# SCH_Plantcare_Module-v3_2024-10-27.net
KiCad netlist of a schematic drawn in EasyEDA
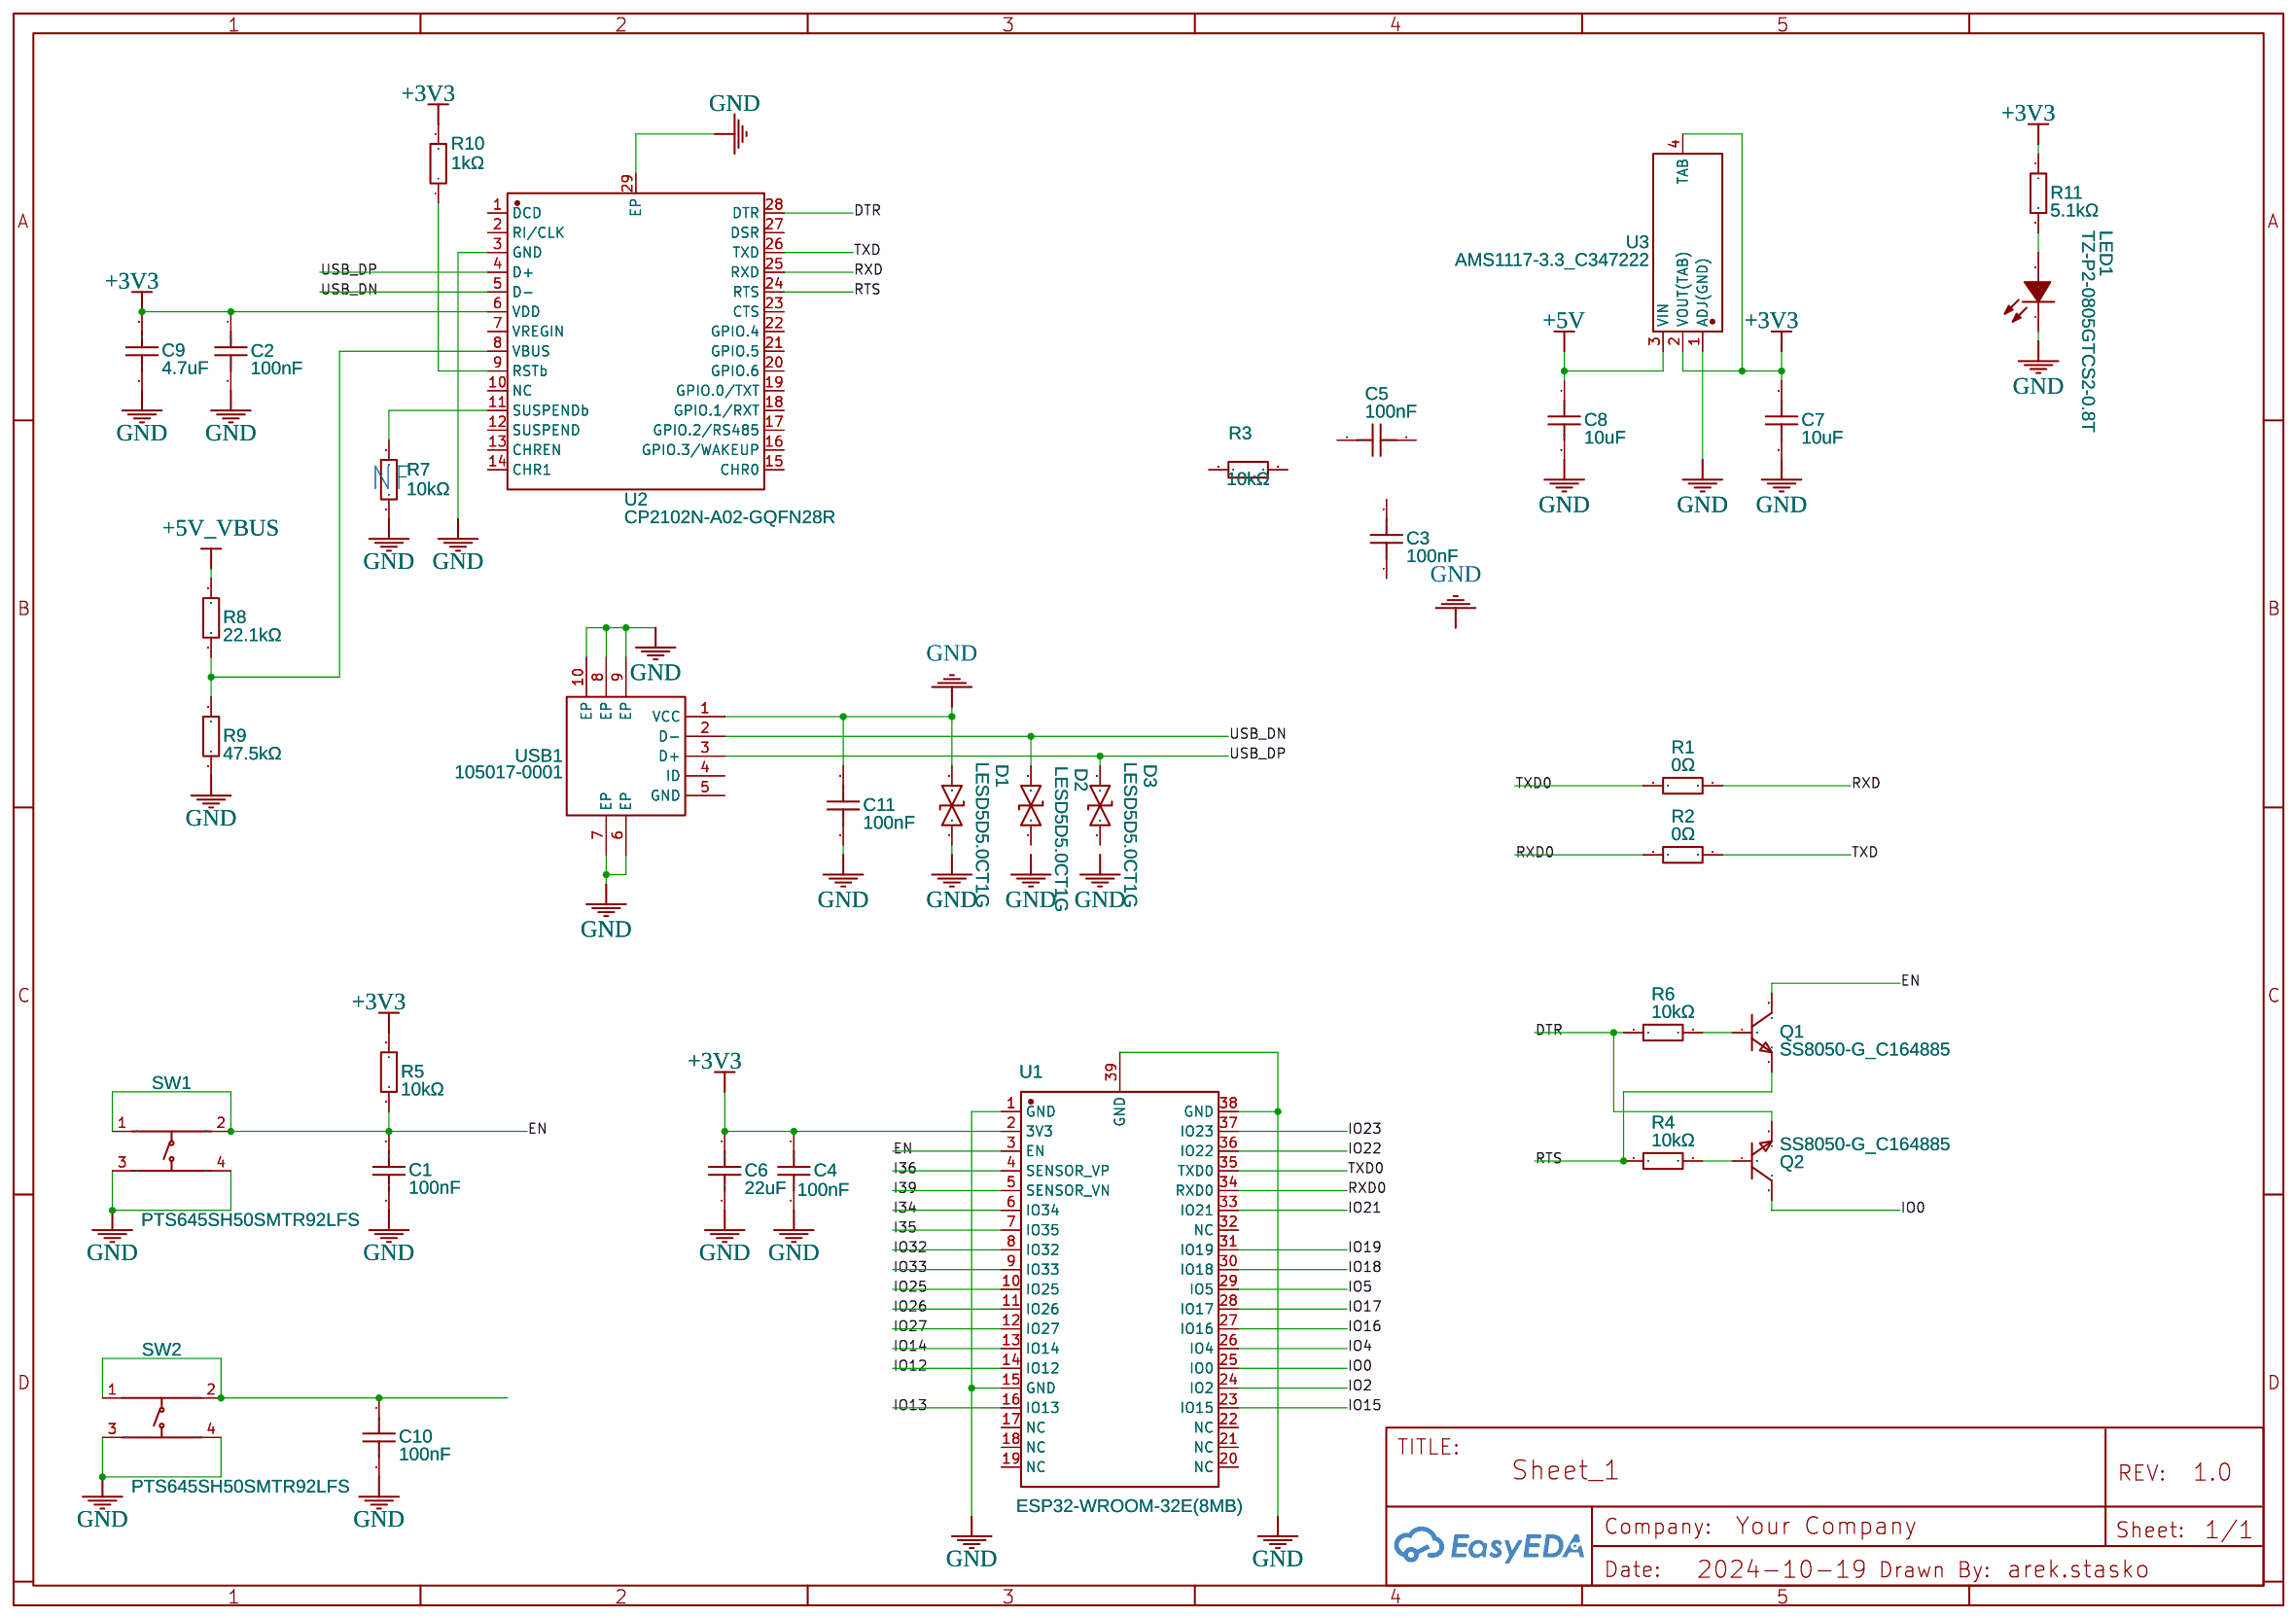
[diagram p0: schematic sheet]

(export (version "E")
  (design (tool "Eeschema 10.0.6"))
  (components
    (comp (ref "C1")
      (value "100nF")
      (fields
        (field (name "Manufacturer Part") "CL05B104KO5NNNC")
        (field (name "Manufacturer") "SAMSUNG(三星)")
      )
      (libsource (lib "") (part "CL05B104KO5NNNC"))
    )
    (comp (ref "C2")
      (value "100nF")
      (fields
        (field (name "Manufacturer Part") "CL05B104KO5NNNC")
        (field (name "Manufacturer") "SAMSUNG(三星)")
      )
      (libsource (lib "") (part "CL05B104KO5NNNC"))
    )
    (comp (ref "C3")
      (value "100nF")
      (fields
        (field (name "Manufacturer Part") "CL05B104KO5NNNC")
        (field (name "Manufacturer") "SAMSUNG(三星)")
      )
      (libsource (lib "") (part "CL05B104KO5NNNC"))
    )
    (comp (ref "C4")
      (value "100nF")
      (fields
        (field (name "Manufacturer Part") "CL05B104KO5NNNC")
        (field (name "Manufacturer") "SAMSUNG(三星)")
      )
      (libsource (lib "") (part "CL05B104KO5NNNC"))
    )
    (comp (ref "C5")
      (value "100nF")
      (fields
        (field (name "Manufacturer Part") "CL05B104KO5NNNC")
        (field (name "Manufacturer") "SAMSUNG(三星)")
      )
      (libsource (lib "") (part "CL05B104KO5NNNC_1"))
    )
    (comp (ref "C6")
      (value "22uF")
      (fields
        (field (name "Manufacturer Part") "CL21A226MAYNNNE")
        (field (name "Manufacturer") "SAMSUNG(三星)")
      )
      (libsource (lib "") (part "CL21A226MAYNNNE"))
    )
    (comp (ref "C7")
      (value "10uF")
      (fields
        (field (name "Manufacturer Part") "CL05A106MP5NUNC")
        (field (name "Manufacturer") "SAMSUNG(三星)")
      )
      (libsource (lib "") (part "CL05A106MP5NUNC_C315248"))
    )
    (comp (ref "C8")
      (value "10uF")
      (fields
        (field (name "Manufacturer Part") "CL05A106MP5NUNC")
        (field (name "Manufacturer") "SAMSUNG(三星)")
      )
      (libsource (lib "") (part "CL05A106MP5NUNC_C315248"))
    )
    (comp (ref "C9")
      (value "4.7uF")
      (fields
        (field (name "Manufacturer Part") "CL05A475KP5NRNC")
        (field (name "Manufacturer") "SAMSUNG(三星)")
      )
      (libsource (lib "") (part "CL05A475KP5NRNC"))
    )
    (comp (ref "C10")
      (value "100nF")
      (fields
        (field (name "Manufacturer Part") "CL05B104KO5NNNC")
        (field (name "Manufacturer") "SAMSUNG(三星)")
      )
      (libsource (lib "") (part "CL05B104KO5NNNC"))
    )
    (comp (ref "C11")
      (value "100nF")
      (fields
        (field (name "Manufacturer Part") "CL05B104KO5NNNC")
        (field (name "Manufacturer") "SAMSUNG(三星)")
      )
      (libsource (lib "") (part "CL05B104KO5NNNC"))
    )
    (comp (ref "D1")
      (value "LESD5D5.0CT1G")
      (fields (field (name "Manufacturer") "LRC(乐山无线电)"))
      (libsource (lib "") (part "LESD5D5.0CT1G_1"))
    )
    (comp (ref "D2")
      (value "LESD5D5.0CT1G")
      (fields (field (name "Manufacturer") "LRC(乐山无线电)"))
      (libsource (lib "") (part "LESD5D5.0CT1G"))
    )
    (comp (ref "D3")
      (value "LESD5D5.0CT1G")
      (fields (field (name "Manufacturer") "LRC(乐山无线电)"))
      (libsource (lib "") (part "LESD5D5.0CT1G"))
    )
    (comp (ref "LED1")
      (value "TZ-P2-0805GTCS2-0.8T")
      (fields (field (name "Manufacturer") "TUOZHAN(拓展光电)"))
      (libsource (lib "") (part "TZ-P2-0805GTCS2-0.8T"))
    )
    (comp (ref "Q1")
      (value "SS8050-G_C164885")
      (fields (field (name "Manufacturer Part") "SS8050-G") (field (name "Manufacturer") "CJ(江苏长电/长晶)"))
      (libsource (lib "") (part "SS8050-G_C164885_1"))
    )
    (comp (ref "Q2")
      (value "SS8050-G_C164885")
      (fields (field (name "Manufacturer Part") "SS8050-G") (field (name "Manufacturer") "CJ(江苏长电/长晶)"))
      (libsource (lib "") (part "SS8050-G_C164885"))
    )
    (comp (ref "R1")
      (value "0Ω")
      (fields
        (field (name "Manufacturer Part") "0402WGF0000TCE")
        (field (name "Manufacturer") "UNI-ROYAL(厚声)")
      )
      (libsource (lib "") (part "0402WGF0000TCE"))
    )
    (comp (ref "R2")
      (value "0Ω")
      (fields
        (field (name "Manufacturer Part") "0402WGF0000TCE")
        (field (name "Manufacturer") "UNI-ROYAL(厚声)")
      )
      (libsource (lib "") (part "0402WGF0000TCE"))
    )
    (comp (ref "R3")
      (value "10kΩ")
      (fields
        (field (name "Manufacturer Part") "0402WGF1002TCE")
        (field (name "Manufacturer") "UNI-ROYAL(厚声)")
      )
      (libsource (lib "") (part "0402WGF1002TCE_1"))
    )
    (comp (ref "R4")
      (value "10kΩ")
      (fields
        (field (name "Manufacturer Part") "0402WGF1002TCE")
        (field (name "Manufacturer") "UNI-ROYAL(厚声)")
      )
      (libsource (lib "") (part "0402WGF1002TCE_1"))
    )
    (comp (ref "R5")
      (value "10kΩ")
      (fields
        (field (name "Manufacturer Part") "0402WGF1002TCE")
        (field (name "Manufacturer") "UNI-ROYAL(厚声)")
      )
      (libsource (lib "") (part "0402WGF1002TCE"))
    )
    (comp (ref "R6")
      (value "10kΩ")
      (fields
        (field (name "Manufacturer Part") "0402WGF1002TCE")
        (field (name "Manufacturer") "UNI-ROYAL(厚声)")
      )
      (libsource (lib "") (part "0402WGF1002TCE_1"))
    )
    (comp (ref "R7")
      (value "10kΩ")
      (fields
        (field (name "Manufacturer Part") "0402WGF1002TCE")
        (field (name "Manufacturer") "UNI-ROYAL(厚声)")
      )
      (libsource (lib "") (part "0402WGF1002TCE"))
    )
    (comp (ref "R8")
      (value "22.1kΩ")
      (fields
        (field (name "Manufacturer Part") "0402WGF2212TCE")
        (field (name "Manufacturer") "UNI-ROYAL(厚声)")
      )
      (libsource (lib "") (part "0402WGF2212TCE"))
    )
    (comp (ref "R9")
      (value "47.5kΩ")
      (fields
        (field (name "Manufacturer Part") "0402WGF4752TCE")
        (field (name "Manufacturer") "UNI-ROYAL(厚声)")
      )
      (libsource (lib "") (part "0402WGF4752TCE"))
    )
    (comp (ref "R10")
      (value "1kΩ")
      (fields
        (field (name "Manufacturer Part") "0402WGF1001TCE")
        (field (name "Manufacturer") "UNI-ROYAL(厚声)")
      )
      (libsource (lib "") (part "0402WGF1001TCE"))
    )
    (comp (ref "R11")
      (value "5.1kΩ")
      (fields
        (field (name "Manufacturer Part") "0402WGF5101TCE")
        (field (name "Manufacturer") "UNI-ROYAL(厚声)")
      )
      (libsource (lib "") (part "0402WGF5101TCE"))
    )
    (comp (ref "SW1")
      (value "PTS645SH50SMTR92LFS")
      (fields (field (name "Manufacturer") "C&K"))
      (libsource (lib "") (part "PTS645SH50SMTR92LFS"))
    )
    (comp (ref "SW2")
      (value "PTS645SH50SMTR92LFS")
      (fields (field (name "Manufacturer") "C&K"))
      (libsource (lib "") (part "PTS645SH50SMTR92LFS"))
    )
    (comp (ref "U1")
      (value "ESP32-WROOM-32E(8MB)")
      (fields
        (field (name "Manufacturer Part") "ESP32-WROOM-32E-N8")
        (field (name "Manufacturer") "ESPRESSIF(乐鑫)")
      )
      (libsource (lib "") (part "ESP32-WROOM-32E(8MB)"))
    )
    (comp (ref "U2")
      (value "CP2102N-A02-GQFN28R")
      (fields (field (name "Manufacturer") "SKYWORKS/SILICON LABS(芯科)"))
      (libsource (lib "") (part "CP2102N-A02-GQFN28R"))
    )
    (comp (ref "U3")
      (value "AMS1117-3.3_C347222")
      (fields (field (name "Manufacturer Part") "AMS1117-3.3") (field (name "Manufacturer") "UMW(友台半导体)"))
      (libsource (lib "") (part "AMS1117-3.3_C347222"))
    )
    (comp (ref "USB1")
      (value "105017-0001")
      (fields (field (name "Manufacturer Part") "1050170001") (field (name "Manufacturer") "MOLEX"))
      (libsource (lib "") (part "105017-0001"))
    )
  )
  (nets
    (net (code "1") (name "+3V3") (class "Default")
      (node (ref "C2") (pin "1") (pinfunction "1_1") (pintype "unspecified"))
      (node (ref "C4") (pin "1") (pinfunction "1_1") (pintype "unspecified"))
      (node (ref "C6") (pin "1") (pinfunction "1_1") (pintype "unspecified"))
      (node (ref "C7") (pin "1") (pinfunction "1_1") (pintype "unspecified"))
      (node (ref "C9") (pin "2") (pinfunction "2_2") (pintype "unspecified"))
      (node (ref "R10") (pin "2") (pinfunction "2_2") (pintype "input"))
      (node (ref "R11") (pin "1") (pinfunction "1_1") (pintype "input"))
      (node (ref "R5") (pin "1") (pinfunction "1_1") (pintype "input"))
      (node (ref "U1") (pin "2") (pinfunction "3V3_2") (pintype "unspecified"))
      (node (ref "U2") (pin "6") (pinfunction "VDD_6") (pintype "unspecified"))
      (node (ref "U3") (pin "2") (pinfunction "VOUT(TAB)_2") (pintype "unspecified"))
      (node (ref "U3") (pin "4") (pinfunction "TAB_4") (pintype "unspecified"))
    )
    (net (code "2") (name "+5V") (class "Default")
      (node (ref "C8") (pin "1") (pinfunction "1_1") (pintype "unspecified"))
      (node (ref "U3") (pin "3") (pinfunction "VIN_3") (pintype "unspecified"))
    )
    (net (code "3") (name "+5V_VBUS") (class "Default")
      (node (ref "R8") (pin "1") (pinfunction "1_1") (pintype "input"))
    )
    (net (code "4") (name "/DTR") (class "Default")
      (node (ref "Q2") (pin "2") (pinfunction "E_2") (pintype "unspecified"))
      (node (ref "R6") (pin "1") (pinfunction "1_1") (pintype "input"))
      (node (ref "U2") (pin "28") (pinfunction "DTR_28") (pintype "unspecified"))
    )
    (net (code "5") (name "/EN") (class "Default")
      (node (ref "C1") (pin "1") (pinfunction "1_1") (pintype "unspecified"))
      (node (ref "Q1") (pin "3") (pinfunction "C_3") (pintype "unspecified"))
      (node (ref "R5") (pin "2") (pinfunction "2_2") (pintype "input"))
      (node (ref "SW1") (pin "1") (pinfunction "1_1") (pintype "unspecified"))
      (node (ref "SW1") (pin "2") (pinfunction "2_2") (pintype "unspecified"))
      (node (ref "U1") (pin "3") (pinfunction "EN_3") (pintype "unspecified"))
    )
    (net (code "6") (name "/I34") (class "Default")
      (node (ref "U1") (pin "6") (pinfunction "IO34_6") (pintype "unspecified"))
    )
    (net (code "7") (name "/I35") (class "Default")
      (node (ref "U1") (pin "7") (pinfunction "IO35_7") (pintype "unspecified"))
    )
    (net (code "8") (name "/I36") (class "Default")
      (node (ref "U1") (pin "4") (pinfunction "SENSOR_VP_4") (pintype "unspecified"))
    )
    (net (code "9") (name "/I39") (class "Default")
      (node (ref "U1") (pin "5") (pinfunction "SENSOR_VN_5") (pintype "unspecified"))
    )
    (net (code "10") (name "/IO0") (class "Default")
      (node (ref "Q2") (pin "3") (pinfunction "C_3") (pintype "unspecified"))
      (node (ref "U1") (pin "25") (pinfunction "IO0_25") (pintype "unspecified"))
    )
    (net (code "11") (name "/IO2") (class "Default")
      (node (ref "U1") (pin "24") (pinfunction "IO2_24") (pintype "unspecified"))
    )
    (net (code "12") (name "/IO4") (class "Default")
      (node (ref "U1") (pin "26") (pinfunction "IO4_26") (pintype "unspecified"))
    )
    (net (code "13") (name "/IO5") (class "Default")
      (node (ref "U1") (pin "29") (pinfunction "IO5_29") (pintype "unspecified"))
    )
    (net (code "14") (name "/IO12") (class "Default")
      (node (ref "U1") (pin "14") (pinfunction "IO12_14") (pintype "unspecified"))
    )
    (net (code "15") (name "/IO13") (class "Default")
      (node (ref "U1") (pin "16") (pinfunction "IO13_16") (pintype "unspecified"))
    )
    (net (code "16") (name "/IO14") (class "Default")
      (node (ref "U1") (pin "13") (pinfunction "IO14_13") (pintype "unspecified"))
    )
    (net (code "17") (name "/IO15") (class "Default")
      (node (ref "U1") (pin "23") (pinfunction "IO15_23") (pintype "unspecified"))
    )
    (net (code "18") (name "/IO16") (class "Default")
      (node (ref "U1") (pin "27") (pinfunction "IO16_27") (pintype "unspecified"))
    )
    (net (code "19") (name "/IO17") (class "Default")
      (node (ref "U1") (pin "28") (pinfunction "IO17_28") (pintype "unspecified"))
    )
    (net (code "20") (name "/IO18") (class "Default")
      (node (ref "U1") (pin "30") (pinfunction "IO18_30") (pintype "unspecified"))
    )
    (net (code "21") (name "/IO19") (class "Default")
      (node (ref "U1") (pin "31") (pinfunction "IO19_31") (pintype "unspecified"))
    )
    (net (code "22") (name "/IO21") (class "Default")
      (node (ref "U1") (pin "33") (pinfunction "IO21_33") (pintype "unspecified"))
    )
    (net (code "23") (name "/IO22") (class "Default")
      (node (ref "U1") (pin "36") (pinfunction "IO22_36") (pintype "unspecified"))
    )
    (net (code "24") (name "/IO23") (class "Default")
      (node (ref "U1") (pin "37") (pinfunction "IO23_37") (pintype "unspecified"))
    )
    (net (code "25") (name "/IO25") (class "Default")
      (node (ref "U1") (pin "10") (pinfunction "IO25_10") (pintype "unspecified"))
    )
    (net (code "26") (name "/IO26") (class "Default")
      (node (ref "U1") (pin "11") (pinfunction "IO26_11") (pintype "unspecified"))
    )
    (net (code "27") (name "/IO27") (class "Default")
      (node (ref "U1") (pin "12") (pinfunction "IO27_12") (pintype "unspecified"))
    )
    (net (code "28") (name "/IO32") (class "Default")
      (node (ref "U1") (pin "8") (pinfunction "IO32_8") (pintype "unspecified"))
    )
    (net (code "29") (name "/IO33") (class "Default")
      (node (ref "U1") (pin "9") (pinfunction "IO33_9") (pintype "unspecified"))
    )
    (net (code "30") (name "/RTS") (class "Default")
      (node (ref "Q1") (pin "2") (pinfunction "E_2") (pintype "unspecified"))
      (node (ref "R4") (pin "1") (pinfunction "1_1") (pintype "input"))
      (node (ref "U2") (pin "24") (pinfunction "RTS_24") (pintype "unspecified"))
    )
    (net (code "31") (name "/RXD") (class "Default")
      (node (ref "R1") (pin "2") (pinfunction "2_2") (pintype "input"))
      (node (ref "U2") (pin "25") (pinfunction "RXD_25") (pintype "unspecified"))
    )
    (net (code "32") (name "/RXD0") (class "Default")
      (node (ref "R2") (pin "1") (pinfunction "1_1") (pintype "input"))
      (node (ref "U1") (pin "34") (pinfunction "RXD0_34") (pintype "unspecified"))
    )
    (net (code "33") (name "/TXD") (class "Default")
      (node (ref "R2") (pin "2") (pinfunction "2_2") (pintype "input"))
      (node (ref "U2") (pin "26") (pinfunction "TXD_26") (pintype "unspecified"))
    )
    (net (code "34") (name "/TXD0") (class "Default")
      (node (ref "R1") (pin "1") (pinfunction "1_1") (pintype "input"))
      (node (ref "U1") (pin "35") (pinfunction "TXD0_35") (pintype "unspecified"))
    )
    (net (code "35") (name "/USB_DN") (class "Default")
      (node (ref "D2") (pin "1") (pinfunction "1_1") (pintype "unspecified"))
      (node (ref "U2") (pin "5") (pinfunction "D-_5") (pintype "unspecified"))
      (node (ref "USB1") (pin "2") (pinfunction "D-_2") (pintype "unspecified"))
    )
    (net (code "36") (name "/USB_DP") (class "Default")
      (node (ref "D3") (pin "1") (pinfunction "1_1") (pintype "unspecified"))
      (node (ref "U2") (pin "4") (pinfunction "D+_4") (pintype "unspecified"))
      (node (ref "USB1") (pin "3") (pinfunction "D+_3") (pintype "unspecified"))
    )
    (net (code "37") (name "GND") (class "Default")
      (node (ref "C1") (pin "2") (pinfunction "2_2") (pintype "unspecified"))
      (node (ref "C10") (pin "2") (pinfunction "2_2") (pintype "unspecified"))
      (node (ref "C11") (pin "1") (pinfunction "1_1") (pintype "unspecified"))
      (node (ref "C11") (pin "2") (pinfunction "2_2") (pintype "unspecified"))
      (node (ref "C2") (pin "2") (pinfunction "2_2") (pintype "unspecified"))
      (node (ref "C4") (pin "2") (pinfunction "2_2") (pintype "unspecified"))
      (node (ref "C6") (pin "2") (pinfunction "2_2") (pintype "unspecified"))
      (node (ref "C7") (pin "2") (pinfunction "2_2") (pintype "unspecified"))
      (node (ref "C8") (pin "2") (pinfunction "2_2") (pintype "unspecified"))
      (node (ref "C9") (pin "1") (pinfunction "1_1") (pintype "unspecified"))
      (node (ref "D1") (pin "1") (pinfunction "1_1") (pintype "unspecified"))
      (node (ref "D1") (pin "2") (pinfunction "2_2") (pintype "unspecified"))
      (node (ref "LED1") (pin "1") (pinfunction "-_1") (pintype "unspecified"))
      (node (ref "R7") (pin "2") (pinfunction "2_2") (pintype "input"))
      (node (ref "R9") (pin "2") (pinfunction "2_2") (pintype "input"))
      (node (ref "SW1") (pin "3") (pinfunction "3_3") (pintype "unspecified"))
      (node (ref "SW1") (pin "4") (pinfunction "4_4") (pintype "unspecified"))
      (node (ref "SW2") (pin "3") (pinfunction "3_3") (pintype "unspecified"))
      (node (ref "SW2") (pin "4") (pinfunction "4_4") (pintype "unspecified"))
      (node (ref "U1") (pin "1") (pinfunction "GND_1") (pintype "unspecified"))
      (node (ref "U1") (pin "15") (pinfunction "GND_15") (pintype "unspecified"))
      (node (ref "U1") (pin "38") (pinfunction "GND_38") (pintype "unspecified"))
      (node (ref "U1") (pin "39") (pinfunction "GND_39") (pintype "unspecified"))
      (node (ref "U2") (pin "29") (pinfunction "EP_29") (pintype "unspecified"))
      (node (ref "U2") (pin "3") (pinfunction "GND_3") (pintype "unspecified"))
      (node (ref "U3") (pin "1") (pinfunction "ADJ(GND)_1") (pintype "unspecified"))
      (node (ref "USB1") (pin "1") (pinfunction "VCC_1") (pintype "unspecified"))
      (node (ref "USB1") (pin "10") (pinfunction "EP_10") (pintype "unspecified"))
      (node (ref "USB1") (pin "6") (pinfunction "EP_6") (pintype "unspecified"))
      (node (ref "USB1") (pin "7") (pinfunction "EP_7") (pintype "unspecified"))
      (node (ref "USB1") (pin "8") (pinfunction "EP_8") (pintype "unspecified"))
      (node (ref "USB1") (pin "9") (pinfunction "EP_9") (pintype "unspecified"))
    )
    (net (code "38") (name "Net-(C10-Pad1)") (class "Default")
      (node (ref "C10") (pin "1") (pinfunction "1_1") (pintype "unspecified"))
      (node (ref "SW2") (pin "1") (pinfunction "1_1") (pintype "unspecified"))
      (node (ref "SW2") (pin "2") (pinfunction "2_2") (pintype "unspecified"))
    )
    (net (code "39") (name "Net-(LED1-+)") (class "Default")
      (node (ref "LED1") (pin "2") (pinfunction "+_2") (pintype "unspecified"))
      (node (ref "R11") (pin "2") (pinfunction "2_2") (pintype "input"))
    )
    (net (code "40") (name "Net-(Q1-B)") (class "Default")
      (node (ref "Q1") (pin "1") (pinfunction "B_1") (pintype "unspecified"))
      (node (ref "R6") (pin "2") (pinfunction "2_2") (pintype "input"))
    )
    (net (code "41") (name "Net-(Q2-B)") (class "Default")
      (node (ref "Q2") (pin "1") (pinfunction "B_1") (pintype "unspecified"))
      (node (ref "R4") (pin "2") (pinfunction "2_2") (pintype "input"))
    )
    (net (code "42") (name "Net-(U2-RSTb)") (class "Default")
      (node (ref "R10") (pin "1") (pinfunction "1_1") (pintype "input"))
      (node (ref "U2") (pin "9") (pinfunction "RSTb_9") (pintype "unspecified"))
    )
    (net (code "43") (name "Net-(U2-SUSPENDb)") (class "Default")
      (node (ref "R7") (pin "1") (pinfunction "1_1") (pintype "input"))
      (node (ref "U2") (pin "11") (pinfunction "SUSPENDb_11") (pintype "unspecified"))
    )
    (net (code "44") (name "Net-(U2-VBUS)") (class "Default")
      (node (ref "R8") (pin "2") (pinfunction "2_2") (pintype "input"))
      (node (ref "R9") (pin "1") (pinfunction "1_1") (pintype "input"))
      (node (ref "U2") (pin "8") (pinfunction "VBUS_8") (pintype "unspecified"))
    )
    (net (code "45") (name "unconnected-(C3-Pad1)") (class "Default")
      (node (ref "C3") (pin "1") (pinfunction "1_1") (pintype "unspecified"))
    )
    (net (code "46") (name "unconnected-(C3-Pad2)") (class "Default")
      (node (ref "C3") (pin "2") (pinfunction "2_2") (pintype "unspecified"))
    )
    (net (code "47") (name "unconnected-(C5-Pad1)") (class "Default")
      (node (ref "C5") (pin "1") (pinfunction "1_1") (pintype "unspecified"))
    )
    (net (code "48") (name "unconnected-(C5-Pad2)") (class "Default")
      (node (ref "C5") (pin "2") (pinfunction "2_2") (pintype "unspecified"))
    )
    (net (code "49") (name "unconnected-(D2-Pad2)") (class "Default")
      (node (ref "D2") (pin "2") (pinfunction "2_2") (pintype "unspecified"))
    )
    (net (code "50") (name "unconnected-(D3-Pad2)") (class "Default")
      (node (ref "D3") (pin "2") (pinfunction "2_2") (pintype "unspecified"))
    )
    (net (code "51") (name "unconnected-(R3-Pad1)") (class "Default")
      (node (ref "R3") (pin "1") (pinfunction "1_1") (pintype "input"))
    )
    (net (code "52") (name "unconnected-(R3-Pad2)") (class "Default")
      (node (ref "R3") (pin "2") (pinfunction "2_2") (pintype "input"))
    )
    (net (code "53") (name "unconnected-(U1-NC-Pad17)") (class "Default")
      (node (ref "U1") (pin "17") (pinfunction "NC_17") (pintype "unspecified"))
    )
    (net (code "54") (name "unconnected-(U1-NC-Pad18)") (class "Default")
      (node (ref "U1") (pin "18") (pinfunction "NC_18") (pintype "unspecified"))
    )
    (net (code "55") (name "unconnected-(U1-NC-Pad19)") (class "Default")
      (node (ref "U1") (pin "19") (pinfunction "NC_19") (pintype "unspecified"))
    )
    (net (code "56") (name "unconnected-(U1-NC-Pad20)") (class "Default")
      (node (ref "U1") (pin "20") (pinfunction "NC_20") (pintype "unspecified"))
    )
    (net (code "57") (name "unconnected-(U1-NC-Pad21)") (class "Default")
      (node (ref "U1") (pin "21") (pinfunction "NC_21") (pintype "unspecified"))
    )
    (net (code "58") (name "unconnected-(U1-NC-Pad22)") (class "Default")
      (node (ref "U1") (pin "22") (pinfunction "NC_22") (pintype "unspecified"))
    )
    (net (code "59") (name "unconnected-(U1-NC-Pad32)") (class "Default")
      (node (ref "U1") (pin "32") (pinfunction "NC_32") (pintype "unspecified"))
    )
    (net (code "60") (name "unconnected-(U2-CHR0-Pad15)") (class "Default")
      (node (ref "U2") (pin "15") (pinfunction "CHR0_15") (pintype "unspecified"))
    )
    (net (code "61") (name "unconnected-(U2-CHR1-Pad14)") (class "Default")
      (node (ref "U2") (pin "14") (pinfunction "CHR1_14") (pintype "unspecified"))
    )
    (net (code "62") (name "unconnected-(U2-CHREN-Pad13)") (class "Default")
      (node (ref "U2") (pin "13") (pinfunction "CHREN_13") (pintype "unspecified"))
    )
    (net (code "63") (name "unconnected-(U2-CTS-Pad23)") (class "Default")
      (node (ref "U2") (pin "23") (pinfunction "CTS_23") (pintype "unspecified"))
    )
    (net (code "64") (name "unconnected-(U2-DCD-Pad1)") (class "Default")
      (node (ref "U2") (pin "1") (pinfunction "DCD_1") (pintype "unspecified"))
    )
    (net (code "65") (name "unconnected-(U2-DSR-Pad27)") (class "Default")
      (node (ref "U2") (pin "27") (pinfunction "DSR_27") (pintype "unspecified"))
    )
    (net (code "66") (name "unconnected-(U2-GPIO.0{slash}TXT-Pad19)") (class "Default")
      (node (ref "U2") (pin "19") (pinfunction "GPIO.0/TXT_19") (pintype "unspecified"))
    )
    (net (code "67") (name "unconnected-(U2-GPIO.1{slash}RXT-Pad18)") (class "Default")
      (node (ref "U2") (pin "18") (pinfunction "GPIO.1/RXT_18") (pintype "unspecified"))
    )
    (net (code "68") (name "unconnected-(U2-GPIO.2{slash}RS485-Pad17)") (class "Default")
      (node (ref "U2") (pin "17") (pinfunction "GPIO.2/RS485_17") (pintype "unspecified"))
    )
    (net (code "69") (name "unconnected-(U2-GPIO.3{slash}WAKEUP-Pad16)") (class "Default")
      (node (ref "U2") (pin "16") (pinfunction "GPIO.3/WAKEUP_16") (pintype "unspecified"))
    )
    (net (code "70") (name "unconnected-(U2-GPIO.4-Pad22)") (class "Default")
      (node (ref "U2") (pin "22") (pinfunction "GPIO.4_22") (pintype "unspecified"))
    )
    (net (code "71") (name "unconnected-(U2-GPIO.5-Pad21)") (class "Default")
      (node (ref "U2") (pin "21") (pinfunction "GPIO.5_21") (pintype "unspecified"))
    )
    (net (code "72") (name "unconnected-(U2-GPIO.6-Pad20)") (class "Default")
      (node (ref "U2") (pin "20") (pinfunction "GPIO.6_20") (pintype "unspecified"))
    )
    (net (code "73") (name "unconnected-(U2-NC-Pad10)") (class "Default")
      (node (ref "U2") (pin "10") (pinfunction "NC_10") (pintype "unspecified"))
    )
    (net (code "74") (name "unconnected-(U2-RI{slash}CLK-Pad2)") (class "Default")
      (node (ref "U2") (pin "2") (pinfunction "RI/CLK_2") (pintype "unspecified"))
    )
    (net (code "75") (name "unconnected-(U2-SUSPEND-Pad12)") (class "Default")
      (node (ref "U2") (pin "12") (pinfunction "SUSPEND_12") (pintype "unspecified"))
    )
    (net (code "76") (name "unconnected-(U2-VREGIN-Pad7)") (class "Default")
      (node (ref "U2") (pin "7") (pinfunction "VREGIN_7") (pintype "unspecified"))
    )
    (net (code "77") (name "unconnected-(USB1-GND-Pad5)") (class "Default")
      (node (ref "USB1") (pin "5") (pinfunction "GND_5") (pintype "unspecified"))
    )
    (net (code "78") (name "unconnected-(USB1-ID-Pad4)") (class "Default")
      (node (ref "USB1") (pin "4") (pinfunction "ID_4") (pintype "unspecified"))
    )
  )
)
